# Motherboard_V2_0.net
KiCad netlist of a schematic drawn in Altium Designer
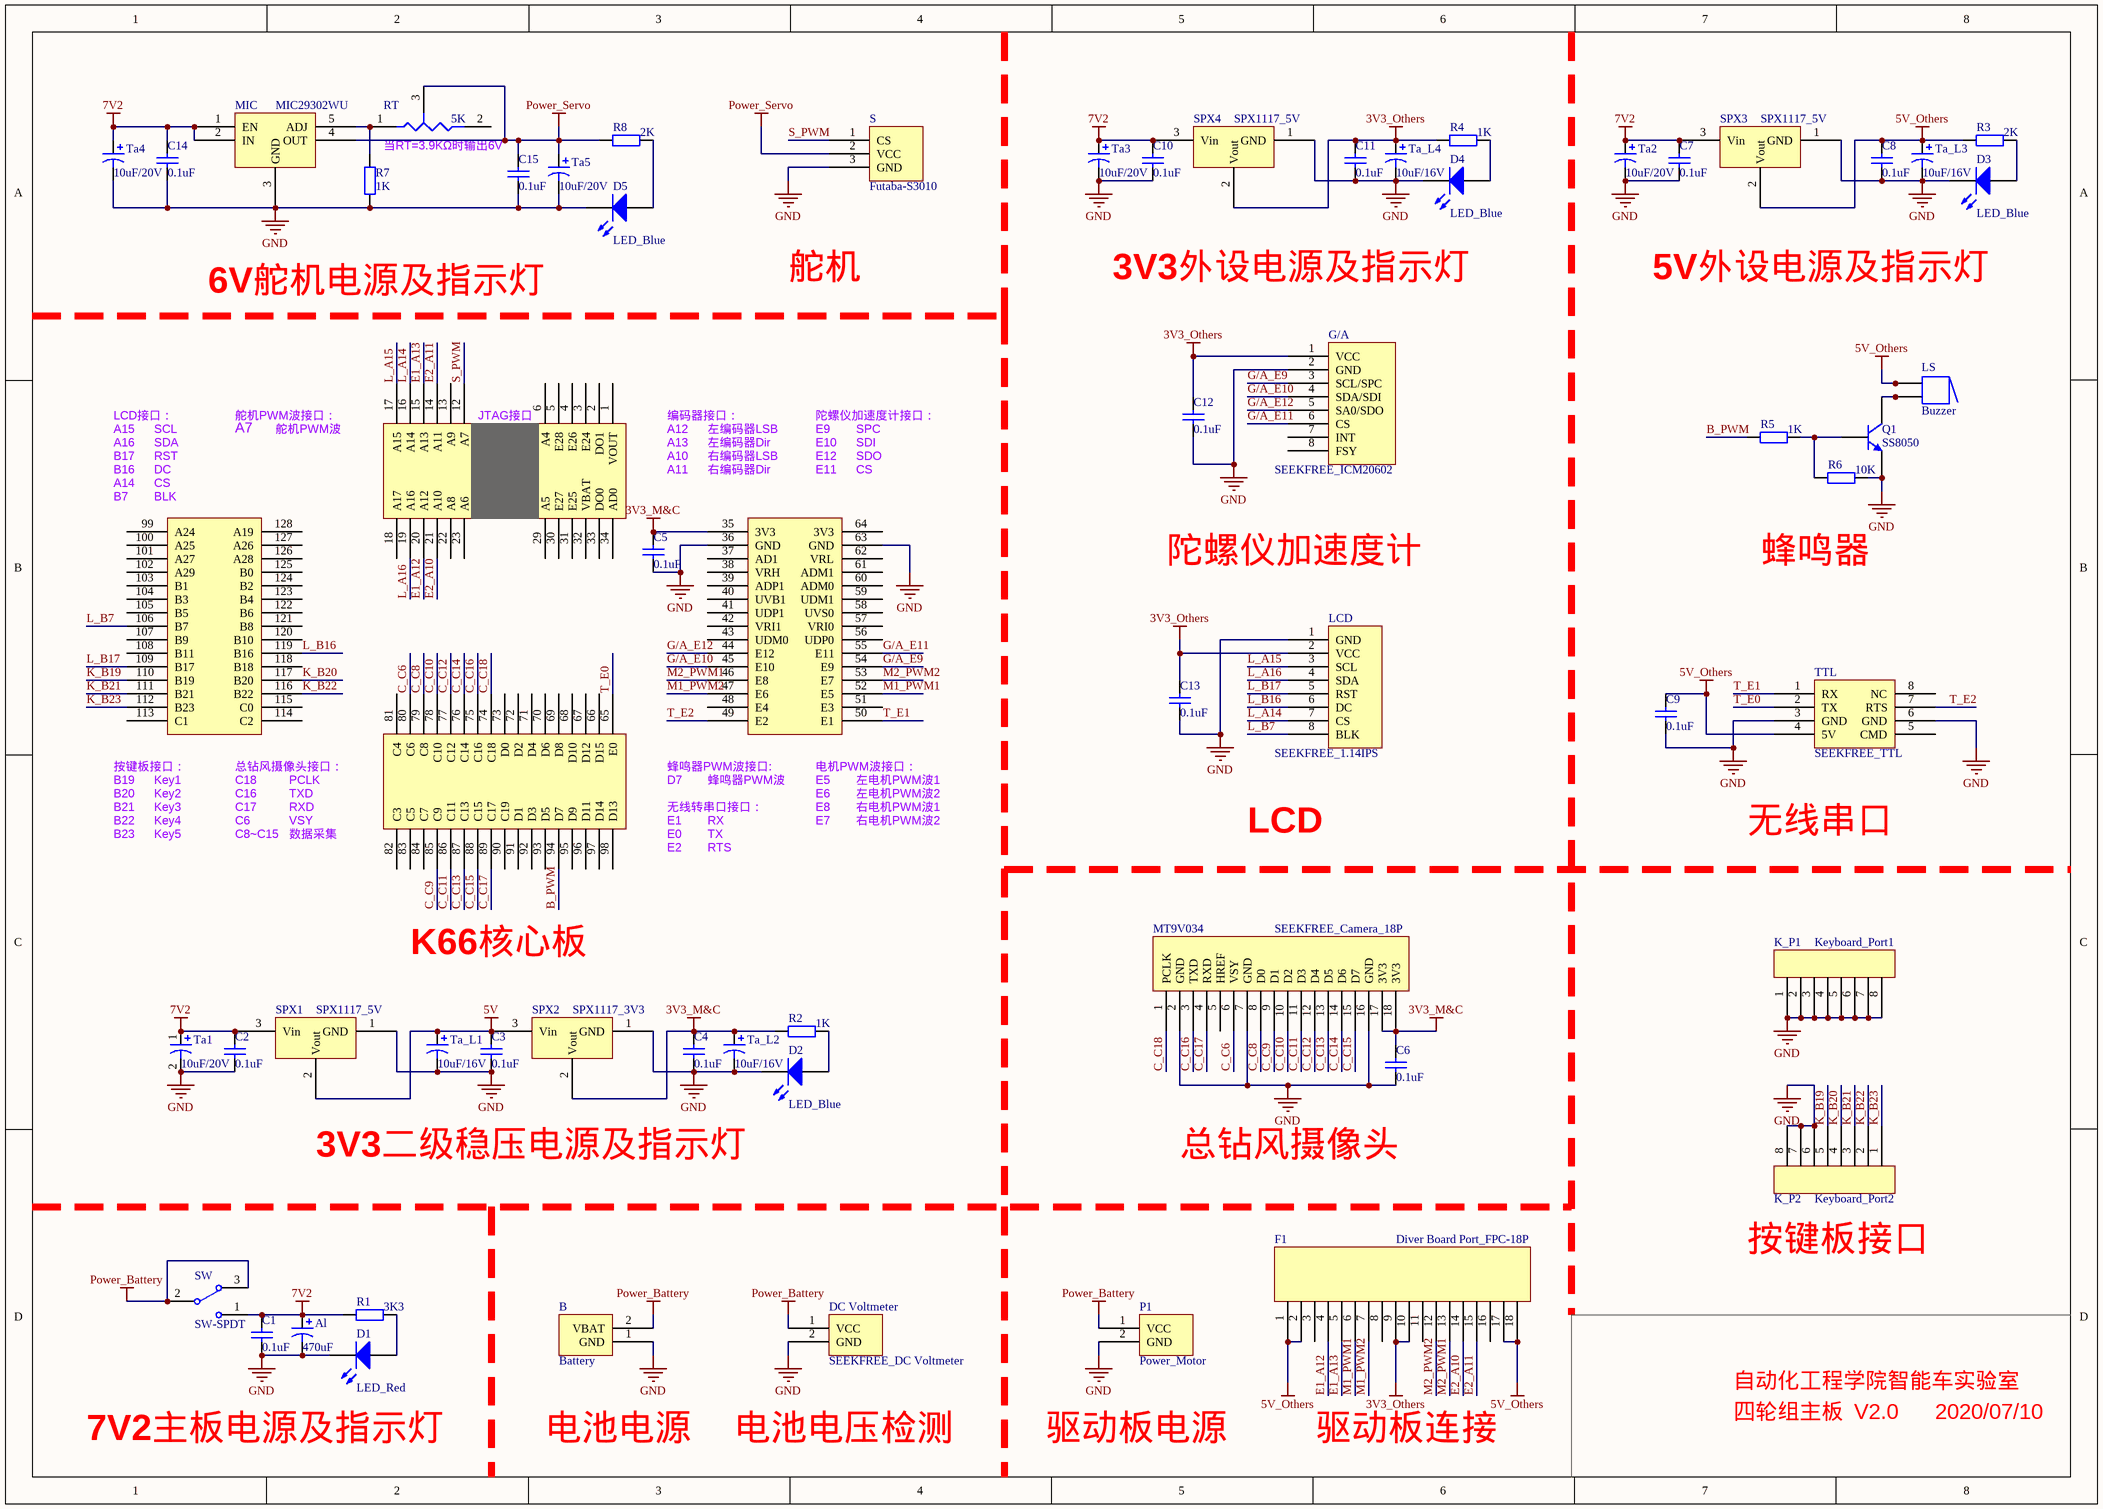
[diagram p0: Motherboard V2.0.SchDoc]

(export (version "E")
  (design (tool "Eeschema 10.0.6"))
  (components
    (comp (ref "Al")
      (value "470uF")
      (footprint "C_AL_8*11.5MM")
      (description "Polarized Capacitor (Surface Mount)")
      (fields (field (name "Comment") "Cap Pol3") (field (name "PUBLISHER") "Altium Limited"))
      (libsource (lib "Miscellaneous Devices") (part "Cap Pol3"))
    )
    (comp (ref "B")
      (value "Battery")
      (footprint "BATTERY_5MM")
      (libsource (lib "Motherboard V2.0") (part "Battery"))
    )
    (comp (ref "C1")
      (value "0.1uF")
      (footprint "C_0603")
      (description "Capacitor")
      (fields (field (name "Comment") "Cap") (field (name "PUBLISHER") "Altium Limited"))
      (libsource (lib "Miscellaneous Devices") (part "Cap"))
    )
    (comp (ref "C2")
      (value "0.1uF")
      (footprint "C_0603")
      (description "Capacitor")
      (fields (field (name "Comment") "Cap") (field (name "PUBLISHER") "Altium Limited"))
      (libsource (lib "Miscellaneous Devices") (part "Cap"))
    )
    (comp (ref "C3")
      (value "0.1uF")
      (footprint "C_0603")
      (description "Capacitor")
      (fields (field (name "Comment") "Cap") (field (name "PUBLISHER") "Altium Limited"))
      (libsource (lib "Miscellaneous Devices") (part "Cap"))
    )
    (comp (ref "C4")
      (value "0.1uF")
      (footprint "C_0603")
      (description "Capacitor")
      (fields (field (name "Comment") "Cap") (field (name "PUBLISHER") "Altium Limited"))
      (libsource (lib "Miscellaneous Devices") (part "Cap"))
    )
    (comp (ref "C5")
      (value "0.1uF")
      (footprint "C_0603")
      (description "Capacitor")
      (fields (field (name "Comment") "Cap") (field (name "PUBLISHER") "Altium Limited"))
      (libsource (lib "Miscellaneous Devices") (part "Cap"))
    )
    (comp (ref "C6")
      (value "0.1uF")
      (footprint "C_0603")
      (description "Capacitor")
      (fields (field (name "Comment") "Cap") (field (name "PUBLISHER") "Altium Limited"))
      (libsource (lib "Miscellaneous Devices") (part "Cap"))
    )
    (comp (ref "C7")
      (value "0.1uF")
      (footprint "C_0603")
      (description "Capacitor")
      (fields (field (name "Comment") "Cap") (field (name "PUBLISHER") "Altium Limited"))
      (libsource (lib "Miscellaneous Devices") (part "Cap"))
    )
    (comp (ref "C8")
      (value "0.1uF")
      (footprint "C_0603")
      (description "Capacitor")
      (fields (field (name "Comment") "Cap") (field (name "PUBLISHER") "Altium Limited"))
      (libsource (lib "Miscellaneous Devices") (part "Cap"))
    )
    (comp (ref "C9")
      (value "0.1uF")
      (footprint "C_0603")
      (description "Capacitor")
      (fields (field (name "Comment") "Cap") (field (name "PUBLISHER") "Altium Limited"))
      (libsource (lib "Miscellaneous Devices") (part "Cap"))
    )
    (comp (ref "C10")
      (value "0.1uF")
      (footprint "C_0603")
      (description "Capacitor")
      (fields (field (name "Comment") "Cap") (field (name "PUBLISHER") "Altium Limited"))
      (libsource (lib "Miscellaneous Devices") (part "Cap"))
    )
    (comp (ref "C11")
      (value "0.1uF")
      (footprint "C_0603")
      (description "Capacitor")
      (fields (field (name "Comment") "Cap") (field (name "PUBLISHER") "Altium Limited"))
      (libsource (lib "Miscellaneous Devices") (part "Cap"))
    )
    (comp (ref "C12")
      (value "0.1uF")
      (footprint "C_0603")
      (description "Capacitor")
      (fields (field (name "Comment") "Cap") (field (name "PUBLISHER") "Altium Limited"))
      (libsource (lib "Miscellaneous Devices") (part "Cap"))
    )
    (comp (ref "C13")
      (value "0.1uF")
      (footprint "C_0603")
      (description "Capacitor")
      (fields (field (name "Comment") "Cap") (field (name "PUBLISHER") "Altium Limited"))
      (libsource (lib "Miscellaneous Devices") (part "Cap"))
    )
    (comp (ref "C14")
      (value "0.1uF")
      (footprint "C_0603")
      (description "Capacitor")
      (fields (field (name "Comment") "Cap") (field (name "PUBLISHER") "Altium Limited"))
      (libsource (lib "Miscellaneous Devices") (part "Cap"))
    )
    (comp (ref "C15")
      (value "0.1uF")
      (footprint "C_0603")
      (description "Capacitor")
      (fields (field (name "Comment") "Cap") (field (name "PUBLISHER") "Altium Limited"))
      (libsource (lib "Miscellaneous Devices") (part "Cap"))
    )
    (comp (ref "D1")
      (value "LED_Red")
      (footprint "LED_0603_R")
      (description "Typical BLUE SiC LED")
      (fields (field (name "PUBLISHER") "Altium Limited"))
      (libsource (lib "Miscellaneous Devices") (part "LED3"))
    )
    (comp (ref "D2")
      (value "LED_Blue")
      (footprint "LED_0603_B")
      (description "Typical BLUE SiC LED")
      (fields (field (name "PUBLISHER") "Altium Limited"))
      (libsource (lib "Miscellaneous Devices") (part "LED3"))
    )
    (comp (ref "D3")
      (value "LED_Blue")
      (footprint "LED_0603_B")
      (description "Typical BLUE SiC LED")
      (fields (field (name "PUBLISHER") "Altium Limited"))
      (libsource (lib "Miscellaneous Devices") (part "LED3"))
    )
    (comp (ref "D4")
      (value "LED_Blue")
      (footprint "LED_0603_B")
      (description "Typical BLUE SiC LED")
      (fields (field (name "PUBLISHER") "Altium Limited"))
      (libsource (lib "Miscellaneous Devices") (part "LED3"))
    )
    (comp (ref "D5")
      (value "LED_Blue")
      (footprint "LED_0603_B")
      (description "Typical BLUE SiC LED")
      (fields (field (name "PUBLISHER") "Altium Limited"))
      (libsource (lib "Miscellaneous Devices") (part "LED3"))
    )
    (comp (ref "DC Voltmeter")
      (value "SEEKFREE_DC Voltmeter")
      (footprint "DC_VOLTMETER_5MM")
      (libsource (lib "Motherboard V2.0") (part "SEEKFREE_DC Voltmeter"))
    )
    (comp (ref "F1")
      (value "Diver Board Port_FPC-18P")
      (footprint "DIVER BOARD PORT_0.5MM")
      (libsource (lib "Motherboard V2.0") (part "Diver Board Port"))
    )
    (comp (ref "G/A")
      (value "SEEKFREE_ICM20602")
      (footprint "G/A_8P_2.54MM")
      (libsource (lib "Motherboard V2.0") (part "SEEKFREE_G/A"))
    )
    (comp (ref "K66")
      (value "SEEKFERR_K66")
      (footprint "K66_BOARD_2.54MM")
      (libsource (lib "Motherboard V2.0") (part "SEEKFERR_K66"))
    )
    (comp (ref "K_P1")
      (value "Keyboard_Port1")
      (footprint "Keyboard_Port1")
      (libsource (lib "Motherboard V2.0") (part "Keyboard_Port1"))
    )
    (comp (ref "K_P2")
      (value "Keyboard_Port2")
      (footprint "Keyboard_Port2")
      (libsource (lib "Motherboard V2.0") (part "Keyboard_Port2"))
    )
    (comp (ref "LCD")
      (value "SEEKFREE_1.14IPS")
      (footprint "LCD_8P_2.54MM")
      (libsource (lib "Motherboard V2.0") (part "SEEKFREE_LCD"))
    )
    (comp (ref "LS")
      (value "Buzzer")
      (footprint "BUZZER_5MM")
      (description "Magnetic Transducer Buzzer")
      (fields (field (name "PUBLISHER") "Altium Limited"))
      (libsource (lib "Miscellaneous Devices") (part "Buzzer"))
    )
    (comp (ref "MIC")
      (value "MIC29302WU")
      (footprint "MIC29302WU_TO263-5")
      (libsource (lib "Motherboard V2.0") (part "MIC29302"))
    )
    (comp (ref "MT9V034")
      (value "SEEKFREE_Camera_18P")
      (footprint "CAMERA_18P_0.5MM")
      (libsource (lib "Motherboard V2.0") (part "SEEKFREE_Camera"))
    )
    (comp (ref "P1")
      (value "Power_Motor")
      (footprint "POWER_MOTOR_5MM")
      (libsource (lib "Motherboard V2.0") (part "Power_Motor"))
    )
    (comp (ref "Q1")
      (value "SS8050")
      (footprint "SS8050_SOT23-3")
      (description "NPN Bipolar Transistor")
      (fields (field (name "PUBLISHER") "Altium Limited"))
      (libsource (lib "Miscellaneous Devices") (part "NPN"))
    )
    (comp (ref "R1")
      (value "3K3")
      (footprint "R_0603")
      (description "Resistor")
      (fields (field (name "Comment") "Res2") (field (name "PUBLISHER") "Altium Limited"))
      (libsource (lib "") (part "Res2_1"))
    )
    (comp (ref "R2")
      (value "1K")
      (footprint "R_0603")
      (description "Resistor")
      (fields (field (name "Comment") "Res2") (field (name "PUBLISHER") "Altium Limited"))
      (libsource (lib "") (part "Res2_1"))
    )
    (comp (ref "R3")
      (value "2K")
      (footprint "R_0603")
      (description "Resistor")
      (fields (field (name "Comment") "Res2") (field (name "PUBLISHER") "Altium Limited"))
      (libsource (lib "") (part "Res2_1"))
    )
    (comp (ref "R4")
      (value "1K")
      (footprint "R_0603")
      (description "Resistor")
      (fields (field (name "Comment") "Res2") (field (name "PUBLISHER") "Altium Limited"))
      (libsource (lib "") (part "Res2_1"))
    )
    (comp (ref "R5")
      (value "1K")
      (footprint "R_0603")
      (description "Resistor")
      (fields (field (name "Comment") "Res2") (field (name "PUBLISHER") "Altium Limited"))
      (libsource (lib "") (part "Res2_1"))
    )
    (comp (ref "R6")
      (value "10K")
      (footprint "R_0603")
      (description "Resistor")
      (fields (field (name "Comment") "Res2") (field (name "PUBLISHER") "Altium Limited"))
      (libsource (lib "") (part "Res2_1"))
    )
    (comp (ref "R7")
      (value "1K")
      (footprint "R_0603")
      (description "Resistor")
      (fields (field (name "Comment") "Res2") (field (name "PUBLISHER") "Altium Limited"))
      (libsource (lib "Miscellaneous Devices") (part "Res2"))
    )
    (comp (ref "R8")
      (value "2K")
      (footprint "R_0603")
      (description "Resistor")
      (fields (field (name "Comment") "Res2") (field (name "PUBLISHER") "Altium Limited"))
      (libsource (lib "") (part "Res2_1"))
    )
    (comp (ref "RT")
      (value "5K")
      (footprint "R_ADJ_3296W")
      (description "Tapped Resistor")
      (fields (field (name "Comment") "Res Tap") (field (name "PUBLISHER") "Altium Limited"))
      (libsource (lib "Miscellaneous Devices") (part "Res Tap"))
    )
    (comp (ref "S")
      (value "Futaba-S3010")
      (footprint "Servo_2.54mm")
      (libsource (lib "Motherboard V2.0") (part "Servo"))
    )
    (comp (ref "SPX1")
      (value "SPX1117_5V")
      (footprint "SPX1117")
      (libsource (lib "Motherboard V2.0") (part "SPX1117_5V"))
    )
    (comp (ref "SPX2")
      (value "SPX1117_3V3")
      (footprint "SPX1117")
      (libsource (lib "Motherboard V2.0") (part "SPX1117_3V3"))
    )
    (comp (ref "SPX3")
      (value "SPX1117_5V")
      (footprint "SPX1117")
      (libsource (lib "Motherboard V2.0") (part "SPX1117_5V"))
    )
    (comp (ref "SPX4")
      (value "SPX1117_5V")
      (footprint "SPX1117")
      (libsource (lib "Motherboard V2.0") (part "SPX1117_5V"))
    )
    (comp (ref "SW")
      (value "SW-SPDT")
      (footprint "SW_4.7mm")
      (description "SPDT Subminiature Toggle Switch, Right Angle Mounting, Vertical Actuation")
      (fields (field (name "PUBLISHER") "Altium Limited"))
      (libsource (lib "Miscellaneous Devices") (part "SW-SPDT"))
    )
    (comp (ref "Ta1")
      (value "10uF/20V")
      (footprint "C_Ta_3528B")
      (description "Polarized Capacitor (Surface Mount)")
      (fields (field (name "Comment") "Cap Pol3") (field (name "PUBLISHER") "Altium Limited"))
      (libsource (lib "") (part "Cap Pol3_1"))
    )
    (comp (ref "Ta2")
      (value "10uF/20V")
      (footprint "C_Ta_3528B")
      (description "Polarized Capacitor (Surface Mount)")
      (fields (field (name "Comment") "Cap Pol3") (field (name "PUBLISHER") "Altium Limited"))
      (libsource (lib "Miscellaneous Devices") (part "Cap Pol3"))
    )
    (comp (ref "Ta3")
      (value "10uF/20V")
      (footprint "C_Ta_3528B")
      (description "Polarized Capacitor (Surface Mount)")
      (fields (field (name "Comment") "Cap Pol3") (field (name "PUBLISHER") "Altium Limited"))
      (libsource (lib "Miscellaneous Devices") (part "Cap Pol3"))
    )
    (comp (ref "Ta4")
      (value "10uF/20V")
      (footprint "C_Ta_3528B")
      (description "Polarized Capacitor (Surface Mount)")
      (fields (field (name "Comment") "Cap Pol3") (field (name "PUBLISHER") "Altium Limited"))
      (libsource (lib "Miscellaneous Devices") (part "Cap Pol3"))
    )
    (comp (ref "Ta5")
      (value "10uF/20V")
      (footprint "C_Ta_3528B")
      (description "Polarized Capacitor (Surface Mount)")
      (fields (field (name "Comment") "Cap Pol3") (field (name "PUBLISHER") "Altium Limited"))
      (libsource (lib "Miscellaneous Devices") (part "Cap Pol3"))
    )
    (comp (ref "Ta_L1")
      (value "10uF/16V")
      (footprint "C_Ta_3216A")
      (description "Polarized Capacitor (Surface Mount)")
      (fields (field (name "Comment") "Cap Pol3") (field (name "PUBLISHER") "Altium Limited"))
      (libsource (lib "Miscellaneous Devices") (part "Cap Pol3"))
    )
    (comp (ref "Ta_L2")
      (value "10uF/16V")
      (footprint "C_Ta_3216A")
      (description "Polarized Capacitor (Surface Mount)")
      (fields (field (name "Comment") "Cap Pol3") (field (name "PUBLISHER") "Altium Limited"))
      (libsource (lib "Miscellaneous Devices") (part "Cap Pol3"))
    )
    (comp (ref "Ta_L3")
      (value "10uF/16V")
      (footprint "C_Ta_3216A")
      (description "Polarized Capacitor (Surface Mount)")
      (fields (field (name "Comment") "Cap Pol3") (field (name "PUBLISHER") "Altium Limited"))
      (libsource (lib "Miscellaneous Devices") (part "Cap Pol3"))
    )
    (comp (ref "Ta_L4")
      (value "10uF/16V")
      (footprint "C_Ta_3216A")
      (description "Polarized Capacitor (Surface Mount)")
      (fields (field (name "Comment") "Cap Pol3") (field (name "PUBLISHER") "Altium Limited"))
      (libsource (lib "Miscellaneous Devices") (part "Cap Pol3"))
    )
    (comp (ref "TTL")
      (value "SEEKFREE_TTL")
      (footprint "TTL_2*4P_2.54MM")
      (libsource (lib "Motherboard V2.0") (part "SEEKFREE_TTL"))
    )
  )
  (nets
    (net (code "1") (name "/B_PWM") (class "Default")
      (node (ref "K66") (pin "94") (pinfunction "D7_94") (pintype "passive"))
      (node (ref "R5") (pin "1") (pinfunction "1_1") (pintype "passive"))
    )
    (net (code "2") (name "/C_C6") (class "Default")
      (node (ref "K66") (pin "80") (pinfunction "C6_80") (pintype "passive"))
      (node (ref "MT9V034") (pin "6") (pinfunction "VSY_6") (pintype "passive"))
    )
    (net (code "3") (name "/C_C8") (class "Default")
      (node (ref "K66") (pin "79") (pinfunction "C8_79") (pintype "passive"))
      (node (ref "MT9V034") (pin "8") (pinfunction "D0_8") (pintype "passive"))
    )
    (net (code "4") (name "/C_C9") (class "Default")
      (node (ref "K66") (pin "85") (pinfunction "C9_85") (pintype "passive"))
      (node (ref "MT9V034") (pin "9") (pinfunction "D1_9") (pintype "passive"))
    )
    (net (code "5") (name "/C_C10") (class "Default")
      (node (ref "K66") (pin "78") (pinfunction "C10_78") (pintype "passive"))
      (node (ref "MT9V034") (pin "10") (pinfunction "D2_10") (pintype "passive"))
    )
    (net (code "6") (name "/C_C11") (class "Default")
      (node (ref "K66") (pin "86") (pinfunction "C11_86") (pintype "passive"))
      (node (ref "MT9V034") (pin "11") (pinfunction "D3_11") (pintype "passive"))
    )
    (net (code "7") (name "/C_C12") (class "Default")
      (node (ref "K66") (pin "77") (pinfunction "C12_77") (pintype "passive"))
      (node (ref "MT9V034") (pin "12") (pinfunction "D4_12") (pintype "passive"))
    )
    (net (code "8") (name "/C_C13") (class "Default")
      (node (ref "K66") (pin "87") (pinfunction "C13_87") (pintype "passive"))
      (node (ref "MT9V034") (pin "13") (pinfunction "D5_13") (pintype "passive"))
    )
    (net (code "9") (name "/C_C14") (class "Default")
      (node (ref "K66") (pin "76") (pinfunction "C14_76") (pintype "passive"))
      (node (ref "MT9V034") (pin "14") (pinfunction "D6_14") (pintype "passive"))
    )
    (net (code "10") (name "/C_C15") (class "Default")
      (node (ref "K66") (pin "88") (pinfunction "C15_88") (pintype "passive"))
      (node (ref "MT9V034") (pin "15") (pinfunction "D7_15") (pintype "passive"))
    )
    (net (code "11") (name "/C_C16") (class "Default")
      (node (ref "K66") (pin "75") (pinfunction "C16_75") (pintype "passive"))
      (node (ref "MT9V034") (pin "3") (pinfunction "TXD_3") (pintype "passive"))
    )
    (net (code "12") (name "/C_C17") (class "Default")
      (node (ref "K66") (pin "89") (pinfunction "C17_89") (pintype "passive"))
      (node (ref "MT9V034") (pin "4") (pinfunction "RXD_4") (pintype "passive"))
    )
    (net (code "13") (name "/C_C18") (class "Default")
      (node (ref "K66") (pin "74") (pinfunction "C18_74") (pintype "passive"))
      (node (ref "MT9V034") (pin "1") (pinfunction "PCLK_1") (pintype "passive"))
    )
    (net (code "14") (name "/E1_A12") (class "Default")
      (node (ref "F1") (pin "4") (pintype "passive"))
      (node (ref "K66") (pin "20") (pinfunction "A12_20") (pintype "passive"))
    )
    (net (code "15") (name "/E1_A13") (class "Default")
      (node (ref "F1") (pin "5") (pintype "passive"))
      (node (ref "K66") (pin "15") (pinfunction "A13_15") (pintype "passive"))
    )
    (net (code "16") (name "/E2_A10") (class "Default")
      (node (ref "F1") (pin "14") (pintype "passive"))
      (node (ref "K66") (pin "21") (pinfunction "A10_21") (pintype "passive"))
    )
    (net (code "17") (name "/E2_A11") (class "Default")
      (node (ref "F1") (pin "15") (pintype "passive"))
      (node (ref "K66") (pin "14") (pinfunction "A11_14") (pintype "passive"))
    )
    (net (code "18") (name "/G{slash}A_E9") (class "Default")
      (node (ref "G/A") (pin "3") (pinfunction "SCL/SPC_3") (pintype "passive"))
      (node (ref "K66") (pin "54") (pinfunction "E9_54") (pintype "passive"))
    )
    (net (code "19") (name "/G{slash}A_E10") (class "Default")
      (node (ref "G/A") (pin "4") (pinfunction "SDA/SDI_4") (pintype "passive"))
      (node (ref "K66") (pin "45") (pinfunction "E10_45") (pintype "passive"))
    )
    (net (code "20") (name "/G{slash}A_E11") (class "Default")
      (node (ref "G/A") (pin "6") (pinfunction "CS_6") (pintype "passive"))
      (node (ref "K66") (pin "55") (pinfunction "E11_55") (pintype "passive"))
    )
    (net (code "21") (name "/G{slash}A_E12") (class "Default")
      (node (ref "G/A") (pin "5") (pinfunction "SA0/SDO_5") (pintype "passive"))
      (node (ref "K66") (pin "44") (pinfunction "E12_44") (pintype "passive"))
    )
    (net (code "22") (name "/K_B19") (class "Default")
      (node (ref "K66") (pin "110") (pinfunction "B19_110") (pintype "passive"))
      (node (ref "K_P2") (pin "5") (pintype "passive"))
    )
    (net (code "23") (name "/K_B20") (class "Default")
      (node (ref "K66") (pin "117") (pinfunction "B20_117") (pintype "passive"))
      (node (ref "K_P2") (pin "4") (pintype "passive"))
    )
    (net (code "24") (name "/K_B21") (class "Default")
      (node (ref "K66") (pin "111") (pinfunction "B21_111") (pintype "passive"))
      (node (ref "K_P2") (pin "3") (pintype "passive"))
    )
    (net (code "25") (name "/K_B22") (class "Default")
      (node (ref "K66") (pin "116") (pinfunction "B22_116") (pintype "passive"))
      (node (ref "K_P2") (pin "2") (pintype "passive"))
    )
    (net (code "26") (name "/K_B23") (class "Default")
      (node (ref "K66") (pin "112") (pinfunction "B23_112") (pintype "passive"))
      (node (ref "K_P2") (pin "1") (pintype "passive"))
    )
    (net (code "27") (name "/L_A14") (class "Default")
      (node (ref "K66") (pin "16") (pinfunction "A14_16") (pintype "passive"))
      (node (ref "LCD") (pin "7") (pinfunction "CS_7") (pintype "passive"))
    )
    (net (code "28") (name "/L_A15") (class "Default")
      (node (ref "K66") (pin "17") (pinfunction "A15_17") (pintype "passive"))
      (node (ref "LCD") (pin "3") (pinfunction "SCL_3") (pintype "passive"))
    )
    (net (code "29") (name "/L_A16") (class "Default")
      (node (ref "K66") (pin "19") (pinfunction "A16_19") (pintype "passive"))
      (node (ref "LCD") (pin "4") (pinfunction "SDA_4") (pintype "passive"))
    )
    (net (code "30") (name "/L_B7") (class "Default")
      (node (ref "K66") (pin "106") (pinfunction "B7_106") (pintype "passive"))
      (node (ref "LCD") (pin "8") (pinfunction "BLK_8") (pintype "passive"))
    )
    (net (code "31") (name "/L_B16") (class "Default")
      (node (ref "K66") (pin "119") (pinfunction "B16_119") (pintype "passive"))
      (node (ref "LCD") (pin "6") (pinfunction "DC_6") (pintype "passive"))
    )
    (net (code "32") (name "/L_B17") (class "Default")
      (node (ref "K66") (pin "109") (pinfunction "B17_109") (pintype "passive"))
      (node (ref "LCD") (pin "5") (pinfunction "RST_5") (pintype "passive"))
    )
    (net (code "33") (name "/M1_PWM1") (class "Default")
      (node (ref "F1") (pin "6") (pintype "passive"))
      (node (ref "K66") (pin "52") (pinfunction "E5_52") (pintype "passive"))
    )
    (net (code "34") (name "/M1_PWM2") (class "Default")
      (node (ref "F1") (pin "7") (pintype "passive"))
      (node (ref "K66") (pin "47") (pinfunction "E6_47") (pintype "passive"))
    )
    (net (code "35") (name "/M2_PWM1") (class "Default")
      (node (ref "F1") (pin "13") (pintype "passive"))
      (node (ref "K66") (pin "46") (pinfunction "E8_46") (pintype "passive"))
    )
    (net (code "36") (name "/M2_PWM2") (class "Default")
      (node (ref "F1") (pin "12") (pintype "passive"))
      (node (ref "K66") (pin "53") (pinfunction "E7_53") (pintype "passive"))
    )
    (net (code "37") (name "/S_PWM") (class "Default")
      (node (ref "K66") (pin "12") (pinfunction "A7_12") (pintype "passive"))
      (node (ref "S") (pin "1") (pinfunction "CS_1") (pintype "passive"))
    )
    (net (code "38") (name "/T_E0") (class "Default")
      (node (ref "K66") (pin "65") (pinfunction "E0_65") (pintype "passive"))
      (node (ref "TTL") (pin "2") (pinfunction "TX_2") (pintype "passive"))
    )
    (net (code "39") (name "/T_E1") (class "Default")
      (node (ref "K66") (pin "50") (pinfunction "E1_50") (pintype "passive"))
      (node (ref "TTL") (pin "1") (pinfunction "RX_1") (pintype "passive"))
    )
    (net (code "40") (name "/T_E2") (class "Default")
      (node (ref "K66") (pin "49") (pinfunction "E2_49") (pintype "passive"))
      (node (ref "TTL") (pin "7") (pinfunction "RTS_7") (pintype "passive"))
    )
    (net (code "41") (name "3V3_M&C") (class "Default")
      (node (ref "C4") (pin "2") (pinfunction "2_2") (pintype "passive"))
      (node (ref "C5") (pin "2") (pinfunction "2_2") (pintype "passive"))
      (node (ref "C6") (pin "2") (pinfunction "2_2") (pintype "passive"))
      (node (ref "K66") (pin "35") (pinfunction "3V3_35") (pintype "passive"))
      (node (ref "MT9V034") (pin "17") (pinfunction "3V3_17") (pintype "passive"))
      (node (ref "MT9V034") (pin "18") (pinfunction "3V3_18") (pintype "passive"))
      (node (ref "R2") (pin "1") (pinfunction "1_1") (pintype "passive"))
      (node (ref "SPX2") (pin "2") (pinfunction "Vout_2") (pintype "passive"))
      (node (ref "Ta_L2") (pin "1") (pinfunction "1_1") (pintype "passive"))
    )
    (net (code "42") (name "3V3_Others") (class "Default")
      (node (ref "C11") (pin "2") (pinfunction "2_2") (pintype "passive"))
      (node (ref "C12") (pin "2") (pinfunction "2_2") (pintype "passive"))
      (node (ref "C13") (pin "2") (pinfunction "2_2") (pintype "passive"))
      (node (ref "F1") (pin "10") (pintype "passive"))
      (node (ref "F1") (pin "9") (pintype "passive"))
      (node (ref "G/A") (pin "1") (pinfunction "VCC_1") (pintype "passive"))
      (node (ref "LCD") (pin "2") (pinfunction "VCC_2") (pintype "passive"))
      (node (ref "R4") (pin "1") (pinfunction "1_1") (pintype "passive"))
      (node (ref "SPX4") (pin "2") (pinfunction "Vout_2") (pintype "passive"))
      (node (ref "Ta_L4") (pin "1") (pinfunction "1_1") (pintype "passive"))
    )
    (net (code "43") (name "5V") (class "Default")
      (node (ref "C3") (pin "2") (pinfunction "2_2") (pintype "passive"))
      (node (ref "SPX1") (pin "2") (pinfunction "Vout_2") (pintype "passive"))
      (node (ref "SPX2") (pin "3") (pinfunction "Vin_3") (pintype "passive"))
      (node (ref "Ta_L1") (pin "1") (pinfunction "1_1") (pintype "passive"))
    )
    (net (code "44") (name "5V_Others") (class "Default")
      (node (ref "C8") (pin "2") (pinfunction "2_2") (pintype "passive"))
      (node (ref "C9") (pin "2") (pinfunction "2_2") (pintype "passive"))
      (node (ref "F1") (pin "1") (pintype "passive"))
      (node (ref "F1") (pin "17") (pintype "passive"))
      (node (ref "F1") (pin "18") (pintype "passive"))
      (node (ref "F1") (pin "2") (pintype "passive"))
      (node (ref "LS") (pin "1") (pinfunction "1_1") (pintype "passive"))
      (node (ref "LS") (pin "1A") (pinfunction "1A_1A") (pintype "passive"))
      (node (ref "R3") (pin "1") (pinfunction "1_1") (pintype "passive"))
      (node (ref "SPX3") (pin "2") (pinfunction "Vout_2") (pintype "passive"))
      (node (ref "TTL") (pin "4") (pinfunction "5V_4") (pintype "passive"))
      (node (ref "Ta_L3") (pin "1") (pinfunction "1_1") (pintype "passive"))
    )
    (net (code "45") (name "7V2") (class "Default")
      (node (ref "Al") (pin "1") (pinfunction "1_1") (pintype "passive"))
      (node (ref "C1") (pin "2") (pinfunction "2_2") (pintype "passive"))
      (node (ref "C10") (pin "2") (pinfunction "2_2") (pintype "passive"))
      (node (ref "C14") (pin "2") (pinfunction "2_2") (pintype "passive"))
      (node (ref "C2") (pin "2") (pinfunction "2_2") (pintype "passive"))
      (node (ref "C7") (pin "2") (pinfunction "2_2") (pintype "passive"))
      (node (ref "MIC") (pin "1") (pinfunction "EN_1") (pintype "passive"))
      (node (ref "MIC") (pin "2") (pinfunction "IN_2") (pintype "passive"))
      (node (ref "R1") (pin "1") (pinfunction "1_1") (pintype "passive"))
      (node (ref "SPX1") (pin "3") (pinfunction "Vin_3") (pintype "passive"))
      (node (ref "SPX3") (pin "3") (pinfunction "Vin_3") (pintype "passive"))
      (node (ref "SPX4") (pin "3") (pinfunction "Vin_3") (pintype "passive"))
      (node (ref "SW") (pin "1") (pinfunction "1_1") (pintype "passive"))
      (node (ref "Ta1") (pin "1") (pinfunction "1_1") (pintype "passive"))
      (node (ref "Ta2") (pin "1") (pinfunction "1_1") (pintype "passive"))
      (node (ref "Ta3") (pin "1") (pinfunction "1_1") (pintype "passive"))
      (node (ref "Ta4") (pin "1") (pinfunction "1_1") (pintype "passive"))
    )
    (net (code "46") (name "GND") (class "Default")
      (node (ref "Al") (pin "2") (pinfunction "2_2") (pintype "passive"))
      (node (ref "B") (pin "1") (pinfunction "GND_1") (pintype "passive"))
      (node (ref "C1") (pin "1") (pinfunction "1_1") (pintype "passive"))
      (node (ref "C10") (pin "1") (pinfunction "1_1") (pintype "passive"))
      (node (ref "C11") (pin "1") (pinfunction "1_1") (pintype "passive"))
      (node (ref "C12") (pin "1") (pinfunction "1_1") (pintype "passive"))
      (node (ref "C13") (pin "1") (pinfunction "1_1") (pintype "passive"))
      (node (ref "C14") (pin "1") (pinfunction "1_1") (pintype "passive"))
      (node (ref "C15") (pin "1") (pinfunction "1_1") (pintype "passive"))
      (node (ref "C2") (pin "1") (pinfunction "1_1") (pintype "passive"))
      (node (ref "C3") (pin "1") (pinfunction "1_1") (pintype "passive"))
      (node (ref "C4") (pin "1") (pinfunction "1_1") (pintype "passive"))
      (node (ref "C5") (pin "1") (pinfunction "1_1") (pintype "passive"))
      (node (ref "C6") (pin "1") (pinfunction "1_1") (pintype "passive"))
      (node (ref "C7") (pin "1") (pinfunction "1_1") (pintype "passive"))
      (node (ref "C8") (pin "1") (pinfunction "1_1") (pintype "passive"))
      (node (ref "C9") (pin "1") (pinfunction "1_1") (pintype "passive"))
      (node (ref "D1") (pin "2") (pinfunction "K_2") (pintype "passive"))
      (node (ref "D2") (pin "2") (pinfunction "K_2") (pintype "passive"))
      (node (ref "D3") (pin "2") (pinfunction "K_2") (pintype "passive"))
      (node (ref "D4") (pin "2") (pinfunction "K_2") (pintype "passive"))
      (node (ref "D5") (pin "2") (pinfunction "K_2") (pintype "passive"))
      (node (ref "DC Voltmeter") (pin "2") (pinfunction "GND_2") (pintype "passive"))
      (node (ref "G/A") (pin "2") (pinfunction "GND_2") (pintype "passive"))
      (node (ref "K66") (pin "36") (pinfunction "GND_36") (pintype "passive"))
      (node (ref "K66") (pin "63") (pinfunction "GND_63") (pintype "passive"))
      (node (ref "K_P1") (pin "1") (pintype "passive"))
      (node (ref "K_P1") (pin "2") (pintype "passive"))
      (node (ref "K_P1") (pin "3") (pintype "passive"))
      (node (ref "K_P1") (pin "4") (pintype "passive"))
      (node (ref "K_P1") (pin "5") (pintype "passive"))
      (node (ref "K_P1") (pin "6") (pintype "passive"))
      (node (ref "K_P1") (pin "7") (pintype "passive"))
      (node (ref "K_P1") (pin "8") (pintype "passive"))
      (node (ref "K_P2") (pin "6") (pintype "passive"))
      (node (ref "K_P2") (pin "7") (pintype "passive"))
      (node (ref "K_P2") (pin "8") (pintype "passive"))
      (node (ref "LCD") (pin "1") (pinfunction "GND_1") (pintype "passive"))
      (node (ref "MIC") (pin "3") (pinfunction "GND_3") (pintype "passive"))
      (node (ref "MT9V034") (pin "16") (pinfunction "GND_16") (pintype "passive"))
      (node (ref "MT9V034") (pin "2") (pinfunction "GND_2") (pintype "passive"))
      (node (ref "MT9V034") (pin "7") (pinfunction "GND_7") (pintype "passive"))
      (node (ref "P1") (pin "2") (pinfunction "GND_2") (pintype "passive"))
      (node (ref "Q1") (pin "3") (pinfunction "E_3") (pintype "passive"))
      (node (ref "R6") (pin "2") (pinfunction "2_2") (pintype "passive"))
      (node (ref "R7") (pin "1") (pinfunction "1_1") (pintype "passive"))
      (node (ref "S") (pin "3") (pinfunction "GND_3") (pintype "passive"))
      (node (ref "SPX1") (pin "1") (pinfunction "GND_1") (pintype "passive"))
      (node (ref "SPX2") (pin "1") (pinfunction "GND_1") (pintype "passive"))
      (node (ref "SPX3") (pin "1") (pinfunction "GND_1") (pintype "passive"))
      (node (ref "SPX4") (pin "1") (pinfunction "GND_1") (pintype "passive"))
      (node (ref "TTL") (pin "3") (pinfunction "GND_3") (pintype "passive"))
      (node (ref "TTL") (pin "6") (pinfunction "GND_6") (pintype "passive"))
      (node (ref "Ta1") (pin "2") (pinfunction "2_2") (pintype "passive"))
      (node (ref "Ta2") (pin "2") (pinfunction "2_2") (pintype "passive"))
      (node (ref "Ta3") (pin "2") (pinfunction "2_2") (pintype "passive"))
      (node (ref "Ta4") (pin "2") (pinfunction "2_2") (pintype "passive"))
      (node (ref "Ta5") (pin "2") (pinfunction "2_2") (pintype "passive"))
      (node (ref "Ta_L1") (pin "2") (pinfunction "2_2") (pintype "passive"))
      (node (ref "Ta_L2") (pin "2") (pinfunction "2_2") (pintype "passive"))
      (node (ref "Ta_L3") (pin "2") (pinfunction "2_2") (pintype "passive"))
      (node (ref "Ta_L4") (pin "2") (pinfunction "2_2") (pintype "passive"))
    )
    (net (code "47") (name "Net-(D1-A)") (class "Default")
      (node (ref "D1") (pin "1") (pinfunction "A_1") (pintype "passive"))
      (node (ref "R1") (pin "2") (pinfunction "2_2") (pintype "passive"))
    )
    (net (code "48") (name "Net-(D2-A)") (class "Default")
      (node (ref "D2") (pin "1") (pinfunction "A_1") (pintype "passive"))
      (node (ref "R2") (pin "2") (pinfunction "2_2") (pintype "passive"))
    )
    (net (code "49") (name "Net-(D3-A)") (class "Default")
      (node (ref "D3") (pin "1") (pinfunction "A_1") (pintype "passive"))
      (node (ref "R3") (pin "2") (pinfunction "2_2") (pintype "passive"))
    )
    (net (code "50") (name "Net-(D4-A)") (class "Default")
      (node (ref "D4") (pin "1") (pinfunction "A_1") (pintype "passive"))
      (node (ref "R4") (pin "2") (pinfunction "2_2") (pintype "passive"))
    )
    (net (code "51") (name "Net-(D5-A)") (class "Default")
      (node (ref "D5") (pin "1") (pinfunction "A_1") (pintype "passive"))
      (node (ref "R8") (pin "2") (pinfunction "2_2") (pintype "passive"))
    )
    (net (code "52") (name "Net-(MIC-ADJ)") (class "Default")
      (node (ref "MIC") (pin "5") (pinfunction "ADJ_5") (pintype "passive"))
      (node (ref "R7") (pin "2") (pinfunction "2_2") (pintype "passive"))
      (node (ref "RT") (pin "1") (pinfunction "A_1") (pintype "passive"))
    )
    (net (code "53") (name "Net-(Q1-B)") (class "Default")
      (node (ref "Q1") (pin "2") (pinfunction "B_2") (pintype "passive"))
      (node (ref "R5") (pin "2") (pinfunction "2_2") (pintype "passive"))
      (node (ref "R6") (pin "1") (pinfunction "1_1") (pintype "passive"))
    )
    (net (code "54") (name "Net-(Q1-C)") (class "Default")
      (node (ref "LS") (pin "2") (pinfunction "2_2") (pintype "passive"))
      (node (ref "LS") (pin "2A") (pinfunction "2A_2A") (pintype "passive"))
      (node (ref "Q1") (pin "1") (pinfunction "C_1") (pintype "passive"))
    )
    (net (code "55") (name "Power_Battery") (class "Default")
      (node (ref "B") (pin "2") (pinfunction "VBAT_2") (pintype "passive"))
      (node (ref "DC Voltmeter") (pin "1") (pinfunction "VCC_1") (pintype "passive"))
      (node (ref "P1") (pin "1") (pinfunction "VCC_1") (pintype "passive"))
      (node (ref "SW") (pin "2") (pinfunction "2_2") (pintype "passive"))
      (node (ref "SW") (pin "3") (pinfunction "3_3") (pintype "passive"))
    )
    (net (code "56") (name "Power_Servo") (class "Default")
      (node (ref "C15") (pin "2") (pinfunction "2_2") (pintype "passive"))
      (node (ref "MIC") (pin "4") (pinfunction "OUT_4") (pintype "passive"))
      (node (ref "R8") (pin "1") (pinfunction "1_1") (pintype "passive"))
      (node (ref "RT") (pin "3") (pinfunction "TAP_3") (pintype "passive"))
      (node (ref "S") (pin "2") (pinfunction "VCC_2") (pintype "passive"))
      (node (ref "Ta5") (pin "1") (pinfunction "1_1") (pintype "passive"))
    )
    (net (code "57") (name "unconnected-(F1-Pad3)") (class "Default")
      (node (ref "F1") (pin "3") (pintype "passive"))
    )
    (net (code "58") (name "unconnected-(F1-Pad8)") (class "Default")
      (node (ref "F1") (pin "8") (pintype "passive"))
    )
    (net (code "59") (name "unconnected-(F1-Pad11)") (class "Default")
      (node (ref "F1") (pin "11") (pintype "passive"))
    )
    (net (code "60") (name "unconnected-(F1-Pad16)") (class "Default")
      (node (ref "F1") (pin "16") (pintype "passive"))
    )
    (net (code "61") (name "unconnected-(G/A-FSY-Pad8)") (class "Default")
      (node (ref "G/A") (pin "8") (pinfunction "FSY_8") (pintype "passive"))
    )
    (net (code "62") (name "unconnected-(G/A-INT-Pad7)") (class "Default")
      (node (ref "G/A") (pin "7") (pinfunction "INT_7") (pintype "passive"))
    )
    (net (code "63") (name "unconnected-(K66-3V3-Pad64)") (class "Default")
      (node (ref "K66") (pin "64") (pinfunction "3V3_64") (pintype "passive"))
    )
    (net (code "64") (name "unconnected-(K66-A4-Pad6)") (class "Default")
      (node (ref "K66") (pin "6") (pinfunction "A4_6") (pintype "passive"))
    )
    (net (code "65") (name "unconnected-(K66-A5-Pad29)") (class "Default")
      (node (ref "K66") (pin "29") (pinfunction "A5_29") (pintype "passive"))
    )
    (net (code "66") (name "unconnected-(K66-A6-Pad23)") (class "Default")
      (node (ref "K66") (pin "23") (pinfunction "A6_23") (pintype "passive"))
    )
    (net (code "67") (name "unconnected-(K66-A8-Pad22)") (class "Default")
      (node (ref "K66") (pin "22") (pinfunction "A8_22") (pintype "passive"))
    )
    (net (code "68") (name "unconnected-(K66-A9-Pad13)") (class "Default")
      (node (ref "K66") (pin "13") (pinfunction "A9_13") (pintype "passive"))
    )
    (net (code "69") (name "unconnected-(K66-A17-Pad18)") (class "Default")
      (node (ref "K66") (pin "18") (pinfunction "A17_18") (pintype "passive"))
    )
    (net (code "70") (name "unconnected-(K66-A19-Pad128)") (class "Default")
      (node (ref "K66") (pin "128") (pinfunction "A19_128") (pintype "passive"))
    )
    (net (code "71") (name "unconnected-(K66-A24-Pad99)") (class "Default")
      (node (ref "K66") (pin "99") (pinfunction "A24_99") (pintype "passive"))
    )
    (net (code "72") (name "unconnected-(K66-A25-Pad100)") (class "Default")
      (node (ref "K66") (pin "100") (pinfunction "A25_100") (pintype "passive"))
    )
    (net (code "73") (name "unconnected-(K66-A26-Pad127)") (class "Default")
      (node (ref "K66") (pin "127") (pinfunction "A26_127") (pintype "passive"))
    )
    (net (code "74") (name "unconnected-(K66-A27-Pad101)") (class "Default")
      (node (ref "K66") (pin "101") (pinfunction "A27_101") (pintype "passive"))
    )
    (net (code "75") (name "unconnected-(K66-A28-Pad126)") (class "Default")
      (node (ref "K66") (pin "126") (pinfunction "A28_126") (pintype "passive"))
    )
    (net (code "76") (name "unconnected-(K66-A29-Pad102)") (class "Default")
      (node (ref "K66") (pin "102") (pinfunction "A29_102") (pintype "passive"))
    )
    (net (code "77") (name "unconnected-(K66-AD0-Pad34)") (class "Default")
      (node (ref "K66") (pin "34") (pinfunction "AD0_34") (pintype "passive"))
    )
    (net (code "78") (name "unconnected-(K66-AD1-Pad37)") (class "Default")
      (node (ref "K66") (pin "37") (pinfunction "AD1_37") (pintype "passive"))
    )
    (net (code "79") (name "unconnected-(K66-ADM0-Pad60)") (class "Default")
      (node (ref "K66") (pin "60") (pinfunction "ADM0_60") (pintype "passive"))
    )
    (net (code "80") (name "unconnected-(K66-ADM1-Pad61)") (class "Default")
      (node (ref "K66") (pin "61") (pinfunction "ADM1_61") (pintype "passive"))
    )
    (net (code "81") (name "unconnected-(K66-ADP1-Pad39)") (class "Default")
      (node (ref "K66") (pin "39") (pinfunction "ADP1_39") (pintype "passive"))
    )
    (net (code "82") (name "unconnected-(K66-B0-Pad125)") (class "Default")
      (node (ref "K66") (pin "125") (pinfunction "B0_125") (pintype "passive"))
    )
    (net (code "83") (name "unconnected-(K66-B1-Pad103)") (class "Default")
      (node (ref "K66") (pin "103") (pinfunction "B1_103") (pintype "passive"))
    )
    (net (code "84") (name "unconnected-(K66-B2-Pad124)") (class "Default")
      (node (ref "K66") (pin "124") (pinfunction "B2_124") (pintype "passive"))
    )
    (net (code "85") (name "unconnected-(K66-B3-Pad104)") (class "Default")
      (node (ref "K66") (pin "104") (pinfunction "B3_104") (pintype "passive"))
    )
    (net (code "86") (name "unconnected-(K66-B4-Pad123)") (class "Default")
      (node (ref "K66") (pin "123") (pinfunction "B4_123") (pintype "passive"))
    )
    (net (code "87") (name "unconnected-(K66-B5-Pad105)") (class "Default")
      (node (ref "K66") (pin "105") (pinfunction "B5_105") (pintype "passive"))
    )
    (net (code "88") (name "unconnected-(K66-B6-Pad122)") (class "Default")
      (node (ref "K66") (pin "122") (pinfunction "B6_122") (pintype "passive"))
    )
    (net (code "89") (name "unconnected-(K66-B8-Pad121)") (class "Default")
      (node (ref "K66") (pin "121") (pinfunction "B8_121") (pintype "passive"))
    )
    (net (code "90") (name "unconnected-(K66-B9-Pad107)") (class "Default")
      (node (ref "K66") (pin "107") (pinfunction "B9_107") (pintype "passive"))
    )
    (net (code "91") (name "unconnected-(K66-B10-Pad120)") (class "Default")
      (node (ref "K66") (pin "120") (pinfunction "B10_120") (pintype "passive"))
    )
    (net (code "92") (name "unconnected-(K66-B11-Pad108)") (class "Default")
      (node (ref "K66") (pin "108") (pinfunction "B11_108") (pintype "passive"))
    )
    (net (code "93") (name "unconnected-(K66-B18-Pad118)") (class "Default")
      (node (ref "K66") (pin "118") (pinfunction "B18_118") (pintype "passive"))
    )
    (net (code "94") (name "unconnected-(K66-C0-Pad115)") (class "Default")
      (node (ref "K66") (pin "115") (pinfunction "C0_115") (pintype "passive"))
    )
    (net (code "95") (name "unconnected-(K66-C1-Pad113)") (class "Default")
      (node (ref "K66") (pin "113") (pinfunction "C1_113") (pintype "passive"))
    )
    (net (code "96") (name "unconnected-(K66-C2-Pad114)") (class "Default")
      (node (ref "K66") (pin "114") (pinfunction "C2_114") (pintype "passive"))
    )
    (net (code "97") (name "unconnected-(K66-C3-Pad82)") (class "Default")
      (node (ref "K66") (pin "82") (pinfunction "C3_82") (pintype "passive"))
    )
    (net (code "98") (name "unconnected-(K66-C4-Pad81)") (class "Default")
      (node (ref "K66") (pin "81") (pinfunction "C4_81") (pintype "passive"))
    )
    (net (code "99") (name "unconnected-(K66-C5-Pad83)") (class "Default")
      (node (ref "K66") (pin "83") (pinfunction "C5_83") (pintype "passive"))
    )
    (net (code "100") (name "unconnected-(K66-C7-Pad84)") (class "Default")
      (node (ref "K66") (pin "84") (pinfunction "C7_84") (pintype "passive"))
    )
    (net (code "101") (name "unconnected-(K66-C19-Pad90)") (class "Default")
      (node (ref "K66") (pin "90") (pinfunction "C19_90") (pintype "passive"))
    )
    (net (code "102") (name "unconnected-(K66-D0-Pad73)") (class "Default")
      (node (ref "K66") (pin "73") (pinfunction "D0_73") (pintype "passive"))
    )
    (net (code "103") (name "unconnected-(K66-D1-Pad91)") (class "Default")
      (node (ref "K66") (pin "91") (pinfunction "D1_91") (pintype "passive"))
    )
    (net (code "104") (name "unconnected-(K66-D2-Pad72)") (class "Default")
      (node (ref "K66") (pin "72") (pinfunction "D2_72") (pintype "passive"))
    )
    (net (code "105") (name "unconnected-(K66-D3-Pad92)") (class "Default")
      (node (ref "K66") (pin "92") (pinfunction "D3_92") (pintype "passive"))
    )
    (net (code "106") (name "unconnected-(K66-D4-Pad71)") (class "Default")
      (node (ref "K66") (pin "71") (pinfunction "D4_71") (pintype "passive"))
    )
    (net (code "107") (name "unconnected-(K66-D5-Pad93)") (class "Default")
      (node (ref "K66") (pin "93") (pinfunction "D5_93") (pintype "passive"))
    )
    (net (code "108") (name "unconnected-(K66-D6-Pad70)") (class "Default")
      (node (ref "K66") (pin "70") (pinfunction "D6_70") (pintype "passive"))
    )
    (net (code "109") (name "unconnected-(K66-D8-Pad69)") (class "Default")
      (node (ref "K66") (pin "69") (pinfunction "D8_69") (pintype "passive"))
    )
    (net (code "110") (name "unconnected-(K66-D9-Pad95)") (class "Default")
      (node (ref "K66") (pin "95") (pinfunction "D9_95") (pintype "passive"))
    )
    (net (code "111") (name "unconnected-(K66-D10-Pad68)") (class "Default")
      (node (ref "K66") (pin "68") (pinfunction "D10_68") (pintype "passive"))
    )
    (net (code "112") (name "unconnected-(K66-D11-Pad96)") (class "Default")
      (node (ref "K66") (pin "96") (pinfunction "D11_96") (pintype "passive"))
    )
    (net (code "113") (name "unconnected-(K66-D12-Pad67)") (class "Default")
      (node (ref "K66") (pin "67") (pinfunction "D12_67") (pintype "passive"))
    )
    (net (code "114") (name "unconnected-(K66-D13-Pad98)") (class "Default")
      (node (ref "K66") (pin "98") (pinfunction "D13_98") (pintype "passive"))
    )
    (net (code "115") (name "unconnected-(K66-D14-Pad97)") (class "Default")
      (node (ref "K66") (pin "97") (pinfunction "D14_97") (pintype "passive"))
    )
    (net (code "116") (name "unconnected-(K66-D15-Pad66)") (class "Default")
      (node (ref "K66") (pin "66") (pinfunction "D15_66") (pintype "passive"))
    )
    (net (code "117") (name "unconnected-(K66-DO0-Pad33)") (class "Default")
      (node (ref "K66") (pin "33") (pinfunction "DO0_33") (pintype "passive"))
    )
    (net (code "118") (name "unconnected-(K66-DO1-Pad2)") (class "Default")
      (node (ref "K66") (pin "2") (pinfunction "DO1_2") (pintype "passive"))
    )
    (net (code "119") (name "unconnected-(K66-E3-Pad51)") (class "Default")
      (node (ref "K66") (pin "51") (pinfunction "E3_51") (pintype "passive"))
    )
    (net (code "120") (name "unconnected-(K66-E4-Pad48)") (class "Default")
      (node (ref "K66") (pin "48") (pinfunction "E4_48") (pintype "passive"))
    )
    (net (code "121") (name "unconnected-(K66-E24-Pad3)") (class "Default")
      (node (ref "K66") (pin "3") (pinfunction "E24_3") (pintype "passive"))
    )
    (net (code "122") (name "unconnected-(K66-E25-Pad31)") (class "Default")
      (node (ref "K66") (pin "31") (pinfunction "E25_31") (pintype "passive"))
    )
    (net (code "123") (name "unconnected-(K66-E26-Pad4)") (class "Default")
      (node (ref "K66") (pin "4") (pinfunction "E26_4") (pintype "passive"))
    )
    (net (code "124") (name "unconnected-(K66-E27-Pad30)") (class "Default")
      (node (ref "K66") (pin "30") (pinfunction "E27_30") (pintype "passive"))
    )
    (net (code "125") (name "unconnected-(K66-E28-Pad5)") (class "Default")
      (node (ref "K66") (pin "5") (pinfunction "E28_5") (pintype "passive"))
    )
    (net (code "126") (name "unconnected-(K66-UDM0-Pad43)") (class "Default")
      (node (ref "K66") (pin "43") (pinfunction "UDM0_43") (pintype "passive"))
    )
    (net (code "127") (name "unconnected-(K66-UDM1-Pad59)") (class "Default")
      (node (ref "K66") (pin "59") (pinfunction "UDM1_59") (pintype "passive"))
    )
    (net (code "128") (name "unconnected-(K66-UDP0-Pad56)") (class "Default")
      (node (ref "K66") (pin "56") (pinfunction "UDP0_56") (pintype "passive"))
    )
    (net (code "129") (name "unconnected-(K66-UDP1-Pad41)") (class "Default")
      (node (ref "K66") (pin "41") (pinfunction "UDP1_41") (pintype "passive"))
    )
    (net (code "130") (name "unconnected-(K66-UVB1-Pad40)") (class "Default")
      (node (ref "K66") (pin "40") (pinfunction "UVB1_40") (pintype "passive"))
    )
    (net (code "131") (name "unconnected-(K66-UVS0-Pad58)") (class "Default")
      (node (ref "K66") (pin "58") (pinfunction "UVS0_58") (pintype "passive"))
    )
    (net (code "132") (name "unconnected-(K66-VBAT-Pad32)") (class "Default")
      (node (ref "K66") (pin "32") (pinfunction "VBAT_32") (pintype "passive"))
    )
    (net (code "133") (name "unconnected-(K66-VOUT-Pad1)") (class "Default")
      (node (ref "K66") (pin "1") (pinfunction "VOUT_1") (pintype "passive"))
    )
    (net (code "134") (name "unconnected-(K66-VRH-Pad38)") (class "Default")
      (node (ref "K66") (pin "38") (pinfunction "VRH_38") (pintype "passive"))
    )
    (net (code "135") (name "unconnected-(K66-VRI0-Pad57)") (class "Default")
      (node (ref "K66") (pin "57") (pinfunction "VRI0_57") (pintype "passive"))
    )
    (net (code "136") (name "unconnected-(K66-VRI1-Pad42)") (class "Default")
      (node (ref "K66") (pin "42") (pinfunction "VRI1_42") (pintype "passive"))
    )
    (net (code "137") (name "unconnected-(K66-VRL-Pad62)") (class "Default")
      (node (ref "K66") (pin "62") (pinfunction "VRL_62") (pintype "passive"))
    )
    (net (code "138") (name "unconnected-(MT9V034-HREF-Pad5)") (class "Default")
      (node (ref "MT9V034") (pin "5") (pinfunction "HREF_5") (pintype "passive"))
    )
    (net (code "139") (name "unconnected-(RT-B-Pad2)") (class "Default")
      (node (ref "RT") (pin "2") (pinfunction "B_2") (pintype "passive"))
    )
    (net (code "140") (name "unconnected-(TTL-CMD-Pad5)") (class "Default")
      (node (ref "TTL") (pin "5") (pinfunction "CMD_5") (pintype "passive"))
    )
    (net (code "141") (name "unconnected-(TTL-NC-Pad8)") (class "Default")
      (node (ref "TTL") (pin "8") (pinfunction "NC_8") (pintype "passive"))
    )
  )
)
